# dlp_vco_v1_1_4_main.net
KiCad netlist of a schematic drawn in EAGLE
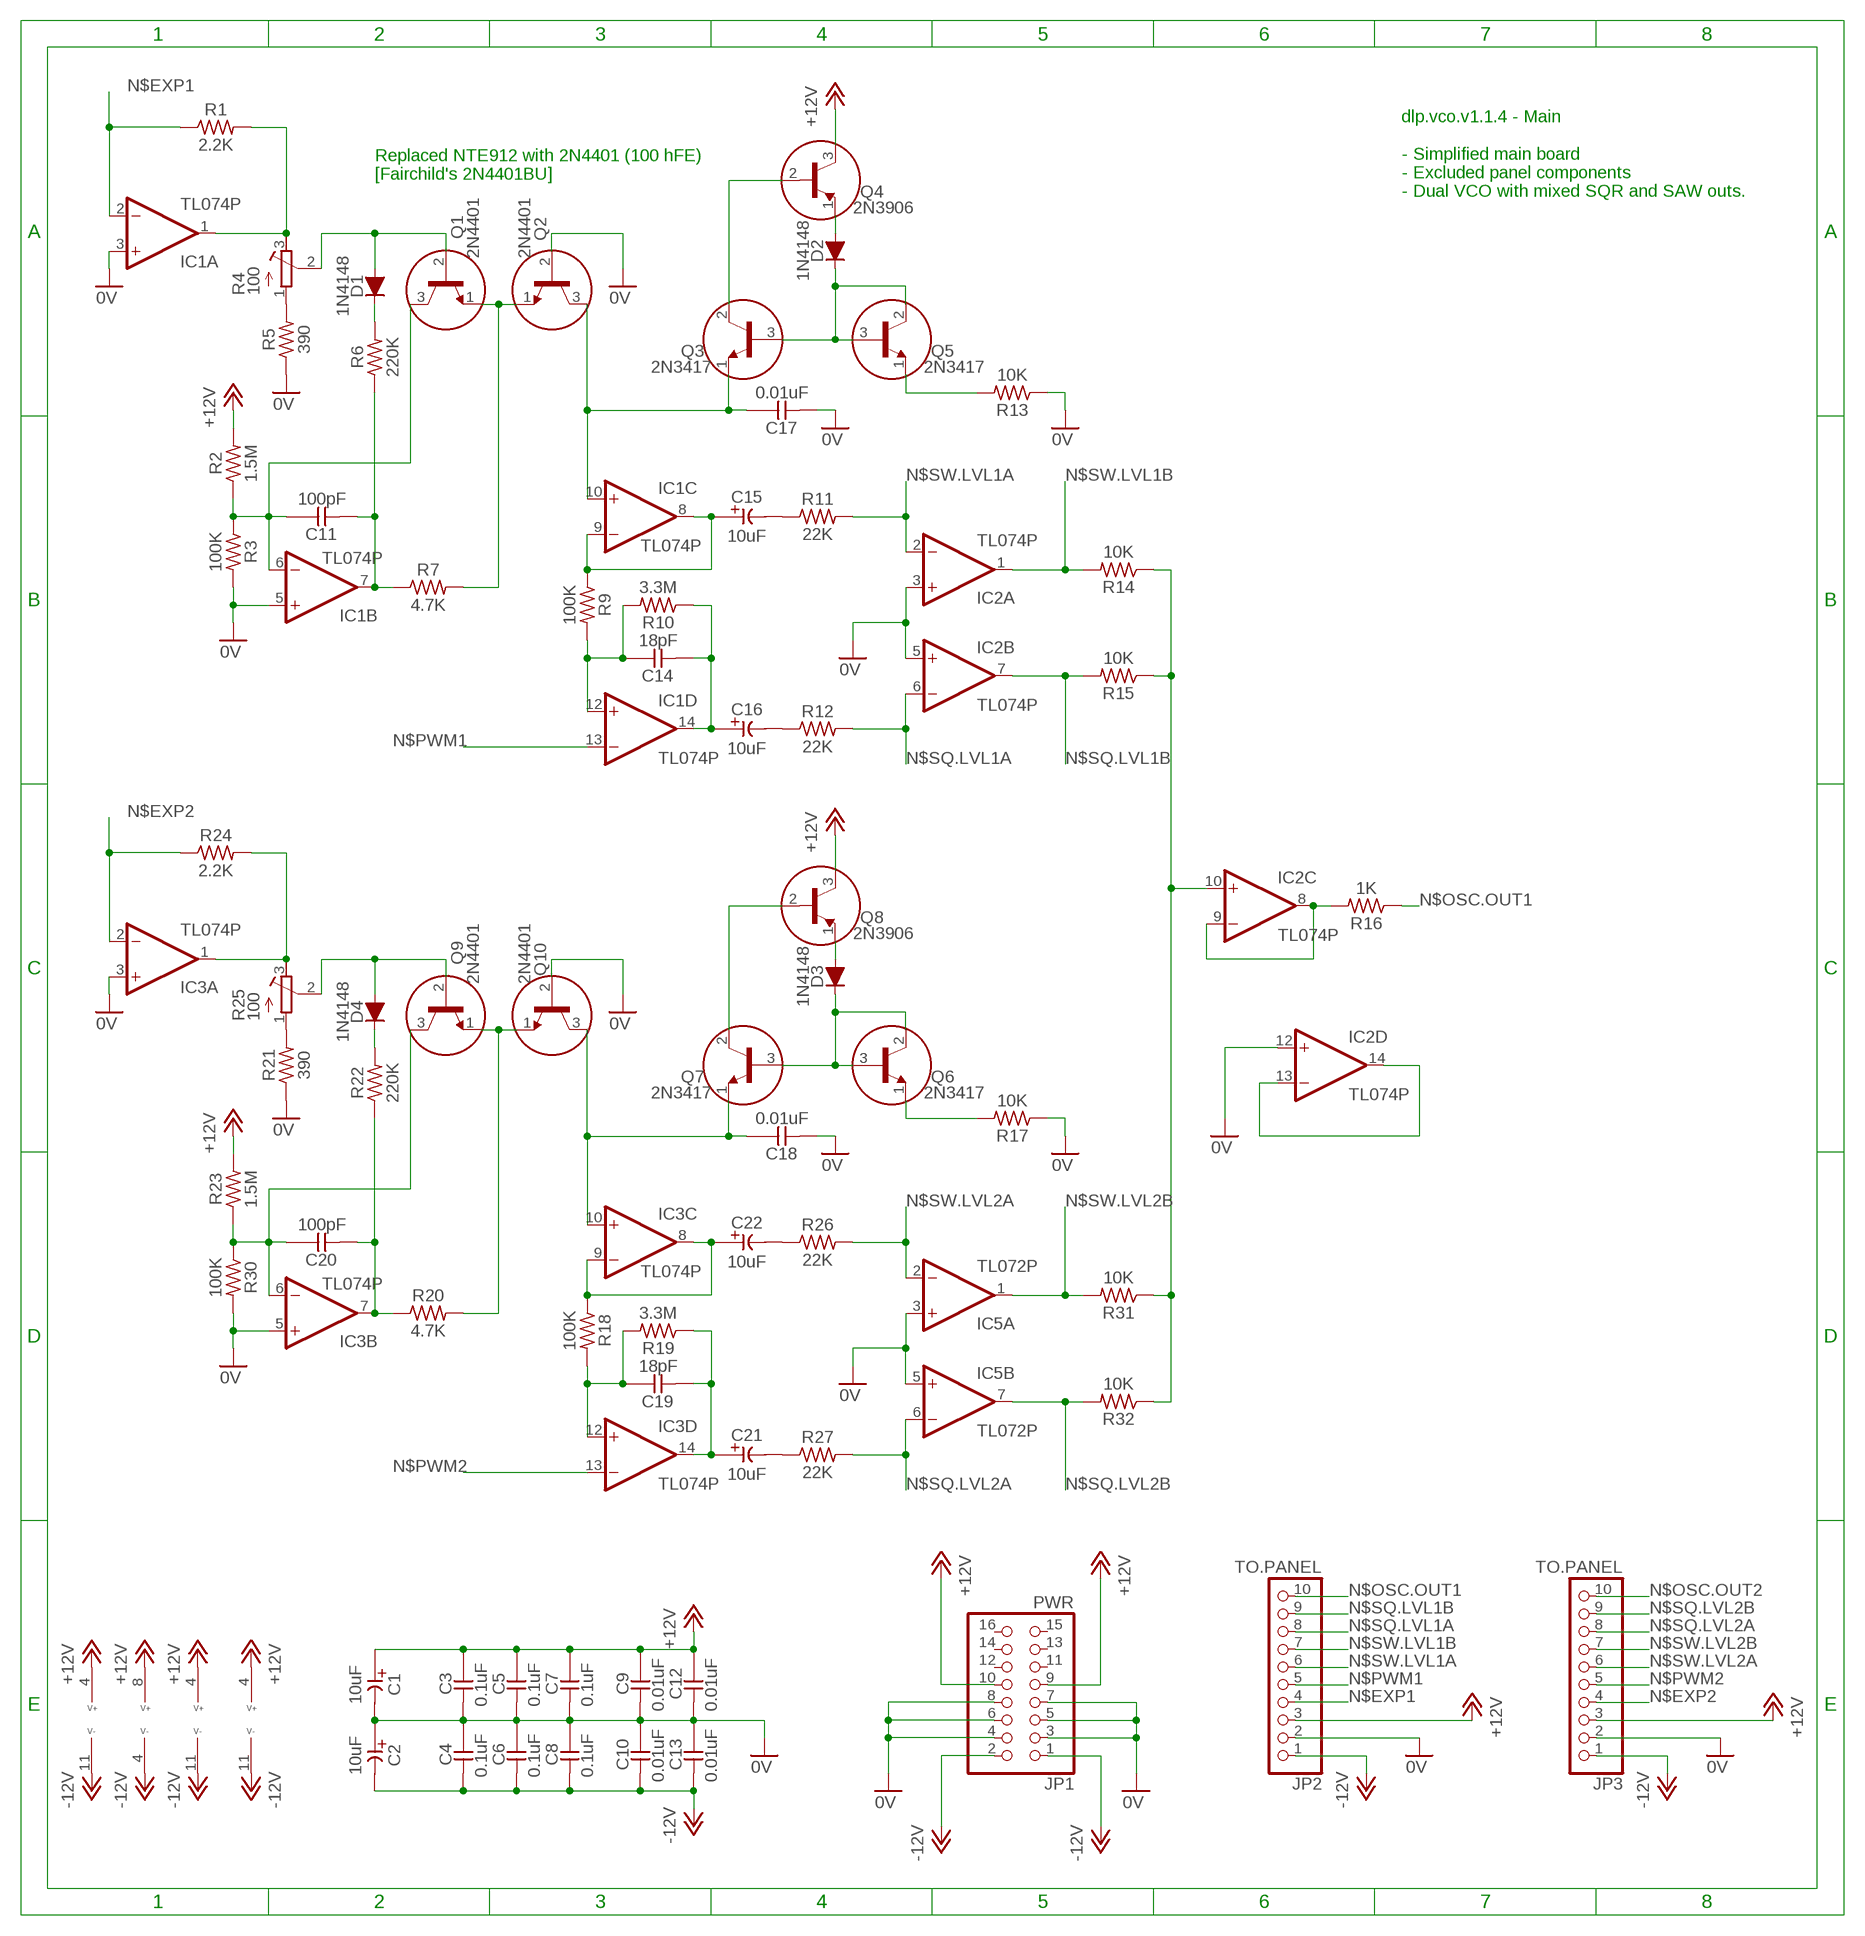
[diagram p0: schematic, sheet 1]

(export (version "E")
  (design (tool "Eeschema 10.0.6"))
  (components
    (comp (ref "C1")
      (value "10uF")
      (footprint "eagle-import:E2-5")
      (libsource (lib "eagle-import") (part "CE-USE2-5"))
    )
    (comp (ref "C2")
      (value "10uF")
      (footprint "eagle-import:E2-5")
      (libsource (lib "eagle-import") (part "CE-USE2-5"))
    )
    (comp (ref "C3")
      (value "0.1uF")
      (footprint "eagle-import:C025-024X044")
      (libsource (lib "eagle-import") (part "CC-US025-024X044"))
    )
    (comp (ref "C4")
      (value "0.1uF")
      (footprint "eagle-import:C025-024X044")
      (libsource (lib "eagle-import") (part "CC-US025-024X044"))
    )
    (comp (ref "C5")
      (value "0.1uF")
      (footprint "eagle-import:C025-024X044")
      (libsource (lib "eagle-import") (part "CC-US025-024X044"))
    )
    (comp (ref "C6")
      (value "0.1uF")
      (footprint "eagle-import:C025-024X044")
      (libsource (lib "eagle-import") (part "CC-US025-024X044"))
    )
    (comp (ref "C7")
      (value "0.1uF")
      (footprint "eagle-import:C025-024X044")
      (libsource (lib "eagle-import") (part "CC-US025-024X044"))
    )
    (comp (ref "C8")
      (value "0.1uF")
      (footprint "eagle-import:C025-024X044")
      (libsource (lib "eagle-import") (part "CC-US025-024X044"))
    )
    (comp (ref "C9")
      (value "0.01uF")
      (footprint "eagle-import:C025-024X044")
      (libsource (lib "eagle-import") (part "CC-US025-024X044"))
    )
    (comp (ref "C10")
      (value "0.01uF")
      (footprint "eagle-import:C025-024X044")
      (libsource (lib "eagle-import") (part "CC-US025-024X044"))
    )
    (comp (ref "C11")
      (value "100pF")
      (footprint "eagle-import:C025-024X044")
      (libsource (lib "eagle-import") (part "CC-US025-024X044"))
    )
    (comp (ref "C12")
      (value "0.01uF")
      (footprint "eagle-import:C025-024X044")
      (libsource (lib "eagle-import") (part "CC-US025-024X044"))
    )
    (comp (ref "C13")
      (value "0.01uF")
      (footprint "eagle-import:C025-024X044")
      (libsource (lib "eagle-import") (part "CC-US025-024X044"))
    )
    (comp (ref "C14")
      (value "18pF")
      (footprint "eagle-import:C025-024X044")
      (libsource (lib "eagle-import") (part "CC-US025-024X044"))
    )
    (comp (ref "C15")
      (value "10uF")
      (footprint "eagle-import:E2-5")
      (libsource (lib "eagle-import") (part "CE-USE2-5"))
    )
    (comp (ref "C16")
      (value "10uF")
      (footprint "eagle-import:E2-5")
      (libsource (lib "eagle-import") (part "CE-USE2-5"))
    )
    (comp (ref "C17")
      (value "0.01uF")
      (footprint "eagle-import:C025-024X044")
      (libsource (lib "eagle-import") (part "CC-US025-024X044"))
    )
    (comp (ref "C18")
      (value "0.01uF")
      (footprint "eagle-import:C025-024X044")
      (libsource (lib "eagle-import") (part "CC-US025-024X044"))
    )
    (comp (ref "C19")
      (value "18pF")
      (footprint "eagle-import:C025-024X044")
      (libsource (lib "eagle-import") (part "CC-US025-024X044"))
    )
    (comp (ref "C20")
      (value "100pF")
      (footprint "eagle-import:C025-024X044")
      (libsource (lib "eagle-import") (part "CC-US025-024X044"))
    )
    (comp (ref "C21")
      (value "10uF")
      (footprint "eagle-import:E2-5")
      (libsource (lib "eagle-import") (part "CE-USE2-5"))
    )
    (comp (ref "C22")
      (value "10uF")
      (footprint "eagle-import:E2-5")
      (libsource (lib "eagle-import") (part "CE-USE2-5"))
    )
    (comp (ref "D1")
      (value "1N4148")
      (footprint "eagle-import:DO35-7")
      (libsource (lib "eagle-import") (part "1N4148"))
    )
    (comp (ref "D2")
      (value "1N4148")
      (footprint "eagle-import:DO35-7")
      (libsource (lib "eagle-import") (part "1N4148"))
    )
    (comp (ref "D3")
      (value "1N4148")
      (footprint "eagle-import:DO35-7")
      (libsource (lib "eagle-import") (part "1N4148"))
    )
    (comp (ref "D4")
      (value "1N4148")
      (footprint "eagle-import:DO35-7")
      (libsource (lib "eagle-import") (part "1N4148"))
    )
    (comp (ref "IC1")
      (value "TL074P")
      (footprint "eagle-import:DIL14")
      (libsource (lib "eagle-import") (part "TL074P"))
    )
    (comp (ref "IC2")
      (value "TL074P")
      (footprint "eagle-import:DIL14")
      (libsource (lib "eagle-import") (part "TL074P"))
    )
    (comp (ref "IC3")
      (value "TL074P")
      (footprint "eagle-import:DIL14")
      (libsource (lib "eagle-import") (part "TL074P"))
    )
    (comp (ref "IC5")
      (value "TL072P")
      (footprint "eagle-import:DIL08")
      (libsource (lib "eagle-import") (part "TL072P"))
    )
    (comp (ref "JP1")
      (value "PWR")
      (footprint "eagle-import:2X08")
      (libsource (lib "eagle-import") (part "PINHD-2X8"))
    )
    (comp (ref "JP2")
      (value "TO.PANEL")
      (footprint "eagle-import:1X10")
      (libsource (lib "eagle-import") (part "PINHD-1X10"))
    )
    (comp (ref "JP3")
      (value "TO.PANEL")
      (footprint "eagle-import:1X10")
      (libsource (lib "eagle-import") (part "PINHD-1X10"))
    )
    (comp (ref "Q1")
      (value "2N4401")
      (footprint "eagle-import:TO92")
      (libsource (lib "eagle-import") (part "2N4401"))
    )
    (comp (ref "Q2")
      (value "2N4401")
      (footprint "eagle-import:TO92")
      (libsource (lib "eagle-import") (part "2N4401"))
    )
    (comp (ref "Q3")
      (value "2N3417")
      (footprint "eagle-import:TO92")
      (libsource (lib "eagle-import") (part "2N3417"))
    )
    (comp (ref "Q4")
      (value "2N3906")
      (footprint "eagle-import:TO92")
      (libsource (lib "eagle-import") (part "2N3906"))
    )
    (comp (ref "Q5")
      (value "2N3417")
      (footprint "eagle-import:TO92")
      (libsource (lib "eagle-import") (part "2N3417"))
    )
    (comp (ref "Q6")
      (value "2N3417")
      (footprint "eagle-import:TO92")
      (libsource (lib "eagle-import") (part "2N3417"))
    )
    (comp (ref "Q7")
      (value "2N3417")
      (footprint "eagle-import:TO92")
      (libsource (lib "eagle-import") (part "2N3417"))
    )
    (comp (ref "Q8")
      (value "2N3906")
      (footprint "eagle-import:TO92")
      (libsource (lib "eagle-import") (part "2N3906"))
    )
    (comp (ref "Q9")
      (value "2N4401")
      (footprint "eagle-import:TO92")
      (libsource (lib "eagle-import") (part "2N4401"))
    )
    (comp (ref "Q10")
      (value "2N4401")
      (footprint "eagle-import:TO92")
      (libsource (lib "eagle-import") (part "2N4401"))
    )
    (comp (ref "R1")
      (value "2.2K")
      (footprint "eagle-import:0309_10")
      (libsource (lib "eagle-import") (part "R0309/10"))
    )
    (comp (ref "R2")
      (value "1.5M")
      (footprint "eagle-import:0309_10")
      (libsource (lib "eagle-import") (part "R0309/10"))
    )
    (comp (ref "R3")
      (value "100K")
      (footprint "eagle-import:0309_10")
      (libsource (lib "eagle-import") (part "R0309/10"))
    )
    (comp (ref "R4")
      (value "100")
      (footprint "eagle-import:RTRIM3296Y")
      (libsource (lib "eagle-import") (part "R-TRIMM3296Y"))
    )
    (comp (ref "R5")
      (value "390")
      (footprint "eagle-import:0309_10")
      (libsource (lib "eagle-import") (part "R0309/10"))
    )
    (comp (ref "R6")
      (value "220K")
      (footprint "eagle-import:0309_10")
      (libsource (lib "eagle-import") (part "R0309/10"))
    )
    (comp (ref "R7")
      (value "4.7K")
      (footprint "eagle-import:0309_10")
      (libsource (lib "eagle-import") (part "R0309/10"))
    )
    (comp (ref "R9")
      (value "100K")
      (footprint "eagle-import:0309_10")
      (libsource (lib "eagle-import") (part "R0309/10"))
    )
    (comp (ref "R10")
      (value "3.3M")
      (footprint "eagle-import:0309_10")
      (libsource (lib "eagle-import") (part "R0309/10"))
    )
    (comp (ref "R11")
      (value "22K")
      (footprint "eagle-import:0309_10")
      (libsource (lib "eagle-import") (part "R0309/10"))
    )
    (comp (ref "R12")
      (value "22K")
      (footprint "eagle-import:0309_10")
      (libsource (lib "eagle-import") (part "R0309/10"))
    )
    (comp (ref "R13")
      (value "10K")
      (footprint "eagle-import:0309_10")
      (libsource (lib "eagle-import") (part "R0309/10"))
    )
    (comp (ref "R14")
      (value "10K")
      (footprint "eagle-import:0309_10")
      (libsource (lib "eagle-import") (part "R0309/10"))
    )
    (comp (ref "R15")
      (value "10K")
      (footprint "eagle-import:0309_10")
      (libsource (lib "eagle-import") (part "R0309/10"))
    )
    (comp (ref "R16")
      (value "1K")
      (footprint "eagle-import:0309_10")
      (libsource (lib "eagle-import") (part "R0309/10"))
    )
    (comp (ref "R17")
      (value "10K")
      (footprint "eagle-import:0309_10")
      (libsource (lib "eagle-import") (part "R0309/10"))
    )
    (comp (ref "R18")
      (value "100K")
      (footprint "eagle-import:0309_10")
      (libsource (lib "eagle-import") (part "R0309/10"))
    )
    (comp (ref "R19")
      (value "3.3M")
      (footprint "eagle-import:0309_10")
      (libsource (lib "eagle-import") (part "R0309/10"))
    )
    (comp (ref "R20")
      (value "4.7K")
      (footprint "eagle-import:0309_10")
      (libsource (lib "eagle-import") (part "R0309/10"))
    )
    (comp (ref "R21")
      (value "390")
      (footprint "eagle-import:0309_10")
      (libsource (lib "eagle-import") (part "R0309/10"))
    )
    (comp (ref "R22")
      (value "220K")
      (footprint "eagle-import:0309_10")
      (libsource (lib "eagle-import") (part "R0309/10"))
    )
    (comp (ref "R23")
      (value "1.5M")
      (footprint "eagle-import:0309_10")
      (libsource (lib "eagle-import") (part "R0309/10"))
    )
    (comp (ref "R24")
      (value "2.2K")
      (footprint "eagle-import:0309_10")
      (libsource (lib "eagle-import") (part "R0309/10"))
    )
    (comp (ref "R25")
      (value "100")
      (footprint "eagle-import:RTRIM3296Y")
      (libsource (lib "eagle-import") (part "R-TRIMM3296Y"))
    )
    (comp (ref "R26")
      (value "22K")
      (footprint "eagle-import:0309_10")
      (libsource (lib "eagle-import") (part "R0309/10"))
    )
    (comp (ref "R27")
      (value "22K")
      (footprint "eagle-import:0309_10")
      (libsource (lib "eagle-import") (part "R0309/10"))
    )
    (comp (ref "R30")
      (value "100K")
      (footprint "eagle-import:0309_10")
      (libsource (lib "eagle-import") (part "R0309/10"))
    )
    (comp (ref "R31")
      (value "10K")
      (footprint "eagle-import:0309_10")
      (libsource (lib "eagle-import") (part "R0309/10"))
    )
    (comp (ref "R32")
      (value "10K")
      (footprint "eagle-import:0309_10")
      (libsource (lib "eagle-import") (part "R0309/10"))
    )
  )
  (nets
    (net (code "1") (name "+12V") (class "Default")
      (node (ref "C1") (pin "+") (pinfunction "+_+") (pintype "passive"))
      (node (ref "C12") (pin "1") (pinfunction "1_1") (pintype "passive"))
      (node (ref "C3") (pin "1") (pinfunction "1_1") (pintype "passive"))
      (node (ref "C5") (pin "1") (pinfunction "1_1") (pintype "passive"))
      (node (ref "C7") (pin "1") (pinfunction "1_1") (pintype "passive"))
      (node (ref "C9") (pin "1") (pinfunction "1_1") (pintype "passive"))
      (node (ref "IC1") (pin "4") (pinfunction "V+_4") (pintype "power_in"))
      (node (ref "IC2") (pin "4") (pinfunction "V+_4") (pintype "power_in"))
      (node (ref "IC3") (pin "4") (pinfunction "V+_4") (pintype "power_in"))
      (node (ref "IC5") (pin "8") (pinfunction "V+_8") (pintype "power_in"))
      (node (ref "JP1") (pin "10") (pinfunction "10_10") (pintype "passive"))
      (node (ref "JP1") (pin "9") (pinfunction "9_9") (pintype "passive"))
      (node (ref "JP2") (pin "3") (pinfunction "3_3") (pintype "passive"))
      (node (ref "JP3") (pin "3") (pinfunction "3_3") (pintype "passive"))
      (node (ref "Q4") (pin "3") (pinfunction "C_3") (pintype "passive"))
      (node (ref "Q8") (pin "3") (pinfunction "C_3") (pintype "passive"))
      (node (ref "R2") (pin "2") (pinfunction "2_2") (pintype "passive"))
      (node (ref "R23") (pin "2") (pinfunction "2_2") (pintype "passive"))
    )
    (net (code "2") (name "-12V") (class "Default")
      (node (ref "C10") (pin "2") (pinfunction "2_2") (pintype "passive"))
      (node (ref "C13") (pin "2") (pinfunction "2_2") (pintype "passive"))
      (node (ref "C2") (pin "-") (pinfunction "-_-") (pintype "passive"))
      (node (ref "C4") (pin "2") (pinfunction "2_2") (pintype "passive"))
      (node (ref "C6") (pin "2") (pinfunction "2_2") (pintype "passive"))
      (node (ref "C8") (pin "2") (pinfunction "2_2") (pintype "passive"))
      (node (ref "IC1") (pin "11") (pinfunction "V-_11") (pintype "power_in"))
      (node (ref "IC2") (pin "11") (pinfunction "V-_11") (pintype "power_in"))
      (node (ref "IC3") (pin "11") (pinfunction "V-_11") (pintype "power_in"))
      (node (ref "IC5") (pin "4") (pinfunction "V-_4") (pintype "power_in"))
      (node (ref "JP1") (pin "1") (pinfunction "1_1") (pintype "passive"))
      (node (ref "JP1") (pin "2") (pinfunction "2_2") (pintype "passive"))
      (node (ref "JP2") (pin "1") (pinfunction "1_1") (pintype "passive"))
      (node (ref "JP3") (pin "1") (pinfunction "1_1") (pintype "passive"))
    )
    (net (code "3") (name "/N$EXP1") (class "Default")
      (node (ref "IC1") (pin "2") (pinfunction "-IN_2") (pintype "input"))
      (node (ref "JP2") (pin "4") (pinfunction "4_4") (pintype "passive"))
      (node (ref "R1") (pin "1") (pinfunction "1_1") (pintype "passive"))
    )
    (net (code "4") (name "/N$EXP2") (class "Default")
      (node (ref "IC3") (pin "2") (pinfunction "-IN_2") (pintype "input"))
      (node (ref "JP3") (pin "4") (pinfunction "4_4") (pintype "passive"))
      (node (ref "R24") (pin "1") (pinfunction "1_1") (pintype "passive"))
    )
    (net (code "5") (name "/N$OSC.OUT1") (class "Default")
      (node (ref "JP2") (pin "10") (pinfunction "10_10") (pintype "passive"))
      (node (ref "R16") (pin "1") (pinfunction "1_1") (pintype "passive"))
    )
    (net (code "6") (name "/N$OSC.OUT2") (class "Default")
      (node (ref "JP3") (pin "10") (pinfunction "10_10") (pintype "passive"))
    )
    (net (code "7") (name "/N$PWM1") (class "Default")
      (node (ref "IC1") (pin "13") (pinfunction "-IN_13") (pintype "input"))
      (node (ref "JP2") (pin "5") (pinfunction "5_5") (pintype "passive"))
    )
    (net (code "8") (name "/N$PWM2") (class "Default")
      (node (ref "IC3") (pin "13") (pinfunction "-IN_13") (pintype "input"))
      (node (ref "JP3") (pin "5") (pinfunction "5_5") (pintype "passive"))
    )
    (net (code "9") (name "/N$SQ.LVL1A") (class "Default")
      (node (ref "IC2") (pin "6") (pinfunction "-IN_6") (pintype "input"))
      (node (ref "JP2") (pin "8") (pinfunction "8_8") (pintype "passive"))
      (node (ref "R12") (pin "2") (pinfunction "2_2") (pintype "passive"))
    )
    (net (code "10") (name "/N$SQ.LVL1B") (class "Default")
      (node (ref "IC2") (pin "7") (pinfunction "OUT_7") (pintype "output"))
      (node (ref "JP2") (pin "9") (pinfunction "9_9") (pintype "passive"))
      (node (ref "R15") (pin "2") (pinfunction "2_2") (pintype "passive"))
    )
    (net (code "11") (name "/N$SQ.LVL2A") (class "Default")
      (node (ref "IC5") (pin "6") (pinfunction "-IN_6") (pintype "input"))
      (node (ref "JP3") (pin "8") (pinfunction "8_8") (pintype "passive"))
      (node (ref "R27") (pin "2") (pinfunction "2_2") (pintype "passive"))
    )
    (net (code "12") (name "/N$SQ.LVL2B") (class "Default")
      (node (ref "IC5") (pin "7") (pinfunction "OUT_7") (pintype "output"))
      (node (ref "JP3") (pin "9") (pinfunction "9_9") (pintype "passive"))
      (node (ref "R32") (pin "2") (pinfunction "2_2") (pintype "passive"))
    )
    (net (code "13") (name "/N$SW.LVL1A") (class "Default")
      (node (ref "IC2") (pin "2") (pinfunction "-IN_2") (pintype "input"))
      (node (ref "JP2") (pin "6") (pinfunction "6_6") (pintype "passive"))
      (node (ref "R11") (pin "2") (pinfunction "2_2") (pintype "passive"))
    )
    (net (code "14") (name "/N$SW.LVL1B") (class "Default")
      (node (ref "IC2") (pin "1") (pinfunction "OUT_1") (pintype "output"))
      (node (ref "JP2") (pin "7") (pinfunction "7_7") (pintype "passive"))
      (node (ref "R14") (pin "2") (pinfunction "2_2") (pintype "passive"))
    )
    (net (code "15") (name "/N$SW.LVL2A") (class "Default")
      (node (ref "IC5") (pin "2") (pinfunction "-IN_2") (pintype "input"))
      (node (ref "JP3") (pin "6") (pinfunction "6_6") (pintype "passive"))
      (node (ref "R26") (pin "2") (pinfunction "2_2") (pintype "passive"))
    )
    (net (code "16") (name "/N$SW.LVL2B") (class "Default")
      (node (ref "IC5") (pin "1") (pinfunction "OUT_1") (pintype "output"))
      (node (ref "JP3") (pin "7") (pinfunction "7_7") (pintype "passive"))
      (node (ref "R31") (pin "2") (pinfunction "2_2") (pintype "passive"))
    )
    (net (code "17") (name "0V") (class "Default")
      (node (ref "C1") (pin "-") (pinfunction "-_-") (pintype "passive"))
      (node (ref "C10") (pin "1") (pinfunction "1_1") (pintype "passive"))
      (node (ref "C12") (pin "2") (pinfunction "2_2") (pintype "passive"))
      (node (ref "C13") (pin "1") (pinfunction "1_1") (pintype "passive"))
      (node (ref "C17") (pin "2") (pinfunction "2_2") (pintype "passive"))
      (node (ref "C18") (pin "2") (pinfunction "2_2") (pintype "passive"))
      (node (ref "C2") (pin "+") (pinfunction "+_+") (pintype "passive"))
      (node (ref "C3") (pin "2") (pinfunction "2_2") (pintype "passive"))
      (node (ref "C4") (pin "1") (pinfunction "1_1") (pintype "passive"))
      (node (ref "C5") (pin "2") (pinfunction "2_2") (pintype "passive"))
      (node (ref "C6") (pin "1") (pinfunction "1_1") (pintype "passive"))
      (node (ref "C7") (pin "2") (pinfunction "2_2") (pintype "passive"))
      (node (ref "C8") (pin "1") (pinfunction "1_1") (pintype "passive"))
      (node (ref "C9") (pin "2") (pinfunction "2_2") (pintype "passive"))
      (node (ref "IC1") (pin "3") (pinfunction "+IN_3") (pintype "input"))
      (node (ref "IC1") (pin "5") (pinfunction "+IN_5") (pintype "input"))
      (node (ref "IC2") (pin "12") (pinfunction "+IN_12") (pintype "input"))
      (node (ref "IC2") (pin "3") (pinfunction "+IN_3") (pintype "input"))
      (node (ref "IC2") (pin "5") (pinfunction "+IN_5") (pintype "input"))
      (node (ref "IC3") (pin "3") (pinfunction "+IN_3") (pintype "input"))
      (node (ref "IC3") (pin "5") (pinfunction "+IN_5") (pintype "input"))
      (node (ref "IC5") (pin "3") (pinfunction "+IN_3") (pintype "input"))
      (node (ref "IC5") (pin "5") (pinfunction "+IN_5") (pintype "input"))
      (node (ref "JP1") (pin "3") (pinfunction "3_3") (pintype "passive"))
      (node (ref "JP1") (pin "4") (pinfunction "4_4") (pintype "passive"))
      (node (ref "JP1") (pin "5") (pinfunction "5_5") (pintype "passive"))
      (node (ref "JP1") (pin "6") (pinfunction "6_6") (pintype "passive"))
      (node (ref "JP1") (pin "7") (pinfunction "7_7") (pintype "passive"))
      (node (ref "JP1") (pin "8") (pinfunction "8_8") (pintype "passive"))
      (node (ref "JP2") (pin "2") (pinfunction "2_2") (pintype "passive"))
      (node (ref "JP3") (pin "2") (pinfunction "2_2") (pintype "passive"))
      (node (ref "Q10") (pin "2") (pinfunction "B_2") (pintype "passive"))
      (node (ref "Q2") (pin "2") (pinfunction "B_2") (pintype "passive"))
      (node (ref "R13") (pin "1") (pinfunction "1_1") (pintype "passive"))
      (node (ref "R17") (pin "1") (pinfunction "1_1") (pintype "passive"))
      (node (ref "R21") (pin "1") (pinfunction "1_1") (pintype "passive"))
      (node (ref "R3") (pin "2") (pinfunction "2_2") (pintype "passive"))
      (node (ref "R30") (pin "2") (pinfunction "2_2") (pintype "passive"))
      (node (ref "R5") (pin "1") (pinfunction "1_1") (pintype "passive"))
    )
    (net (code "18") (name "Net-(C15-Pad-)") (class "Default")
      (node (ref "C15") (pin "-") (pinfunction "-_-") (pintype "passive"))
      (node (ref "R11") (pin "1") (pinfunction "1_1") (pintype "passive"))
    )
    (net (code "19") (name "Net-(C16-Pad-)") (class "Default")
      (node (ref "C16") (pin "-") (pinfunction "-_-") (pintype "passive"))
      (node (ref "R12") (pin "1") (pinfunction "1_1") (pintype "passive"))
    )
    (net (code "20") (name "Net-(C21-Pad-)") (class "Default")
      (node (ref "C21") (pin "-") (pinfunction "-_-") (pintype "passive"))
      (node (ref "R27") (pin "1") (pinfunction "1_1") (pintype "passive"))
    )
    (net (code "21") (name "Net-(C22-Pad-)") (class "Default")
      (node (ref "C22") (pin "-") (pinfunction "-_-") (pintype "passive"))
      (node (ref "R26") (pin "1") (pinfunction "1_1") (pintype "passive"))
    )
    (net (code "22") (name "Net-(D1-PadC)") (class "Default")
      (node (ref "D1") (pin "C") (pinfunction "C_C") (pintype "passive"))
      (node (ref "R6") (pin "2") (pinfunction "2_2") (pintype "passive"))
    )
    (net (code "23") (name "Net-(D4-PadC)") (class "Default")
      (node (ref "D4") (pin "C") (pinfunction "C_C") (pintype "passive"))
      (node (ref "R22") (pin "2") (pinfunction "2_2") (pintype "passive"))
    )
    (net (code "24") (name "Net-(IC1A-OUT)") (class "Default")
      (node (ref "IC1") (pin "1") (pinfunction "OUT_1") (pintype "output"))
      (node (ref "R1") (pin "2") (pinfunction "2_2") (pintype "passive"))
      (node (ref "R4") (pin "3") (pinfunction "E_3") (pintype "passive"))
    )
    (net (code "25") (name "Net-(IC1B--IN)") (class "Default")
      (node (ref "C11") (pin "1") (pinfunction "1_1") (pintype "passive"))
      (node (ref "IC1") (pin "6") (pinfunction "-IN_6") (pintype "input"))
      (node (ref "Q1") (pin "3") (pinfunction "C_3") (pintype "passive"))
      (node (ref "R2") (pin "1") (pinfunction "1_1") (pintype "passive"))
      (node (ref "R3") (pin "1") (pinfunction "1_1") (pintype "passive"))
    )
    (net (code "26") (name "Net-(IC1B-OUT)") (class "Default")
      (node (ref "C11") (pin "2") (pinfunction "2_2") (pintype "passive"))
      (node (ref "IC1") (pin "7") (pinfunction "OUT_7") (pintype "output"))
      (node (ref "R6") (pin "1") (pinfunction "1_1") (pintype "passive"))
      (node (ref "R7") (pin "1") (pinfunction "1_1") (pintype "passive"))
    )
    (net (code "27") (name "Net-(IC1C-+IN)") (class "Default")
      (node (ref "C17") (pin "1") (pinfunction "1_1") (pintype "passive"))
      (node (ref "IC1") (pin "10") (pinfunction "+IN_10") (pintype "input"))
      (node (ref "Q2") (pin "3") (pinfunction "C_3") (pintype "passive"))
      (node (ref "Q3") (pin "1") (pinfunction "E_1") (pintype "passive"))
    )
    (net (code "28") (name "Net-(IC1C--IN)") (class "Default")
      (node (ref "C15") (pin "+") (pinfunction "+_+") (pintype "passive"))
      (node (ref "IC1") (pin "8") (pinfunction "OUT_8") (pintype "output"))
      (node (ref "IC1") (pin "9") (pinfunction "-IN_9") (pintype "input"))
      (node (ref "R9") (pin "1") (pinfunction "1_1") (pintype "passive"))
    )
    (net (code "29") (name "Net-(IC1D-+IN)") (class "Default")
      (node (ref "C14") (pin "1") (pinfunction "1_1") (pintype "passive"))
      (node (ref "IC1") (pin "12") (pinfunction "+IN_12") (pintype "input"))
      (node (ref "R10") (pin "2") (pinfunction "2_2") (pintype "passive"))
      (node (ref "R9") (pin "2") (pinfunction "2_2") (pintype "passive"))
    )
    (net (code "30") (name "Net-(IC1D-OUT)") (class "Default")
      (node (ref "C14") (pin "2") (pinfunction "2_2") (pintype "passive"))
      (node (ref "C16") (pin "+") (pinfunction "+_+") (pintype "passive"))
      (node (ref "IC1") (pin "14") (pinfunction "OUT_14") (pintype "output"))
      (node (ref "R10") (pin "1") (pinfunction "1_1") (pintype "passive"))
    )
    (net (code "31") (name "Net-(IC2C-+IN)") (class "Default")
      (node (ref "IC2") (pin "10") (pinfunction "+IN_10") (pintype "input"))
      (node (ref "R14") (pin "1") (pinfunction "1_1") (pintype "passive"))
      (node (ref "R15") (pin "1") (pinfunction "1_1") (pintype "passive"))
      (node (ref "R31") (pin "1") (pinfunction "1_1") (pintype "passive"))
      (node (ref "R32") (pin "1") (pinfunction "1_1") (pintype "passive"))
    )
    (net (code "32") (name "Net-(IC2C--IN)") (class "Default")
      (node (ref "IC2") (pin "8") (pinfunction "OUT_8") (pintype "output"))
      (node (ref "IC2") (pin "9") (pinfunction "-IN_9") (pintype "input"))
      (node (ref "R16") (pin "2") (pinfunction "2_2") (pintype "passive"))
    )
    (net (code "33") (name "Net-(IC2D--IN)") (class "Default")
      (node (ref "IC2") (pin "13") (pinfunction "-IN_13") (pintype "input"))
      (node (ref "IC2") (pin "14") (pinfunction "OUT_14") (pintype "output"))
    )
    (net (code "34") (name "Net-(IC3A-OUT)") (class "Default")
      (node (ref "IC3") (pin "1") (pinfunction "OUT_1") (pintype "output"))
      (node (ref "R24") (pin "2") (pinfunction "2_2") (pintype "passive"))
      (node (ref "R25") (pin "3") (pinfunction "E_3") (pintype "passive"))
    )
    (net (code "35") (name "Net-(IC3B--IN)") (class "Default")
      (node (ref "C20") (pin "1") (pinfunction "1_1") (pintype "passive"))
      (node (ref "IC3") (pin "6") (pinfunction "-IN_6") (pintype "input"))
      (node (ref "Q9") (pin "3") (pinfunction "C_3") (pintype "passive"))
      (node (ref "R23") (pin "1") (pinfunction "1_1") (pintype "passive"))
      (node (ref "R30") (pin "1") (pinfunction "1_1") (pintype "passive"))
    )
    (net (code "36") (name "Net-(IC3B-OUT)") (class "Default")
      (node (ref "C20") (pin "2") (pinfunction "2_2") (pintype "passive"))
      (node (ref "IC3") (pin "7") (pinfunction "OUT_7") (pintype "output"))
      (node (ref "R20") (pin "1") (pinfunction "1_1") (pintype "passive"))
      (node (ref "R22") (pin "1") (pinfunction "1_1") (pintype "passive"))
    )
    (net (code "37") (name "Net-(IC3C-+IN)") (class "Default")
      (node (ref "C18") (pin "1") (pinfunction "1_1") (pintype "passive"))
      (node (ref "IC3") (pin "10") (pinfunction "+IN_10") (pintype "input"))
      (node (ref "Q10") (pin "3") (pinfunction "C_3") (pintype "passive"))
      (node (ref "Q7") (pin "1") (pinfunction "E_1") (pintype "passive"))
    )
    (net (code "38") (name "Net-(IC3C--IN)") (class "Default")
      (node (ref "C22") (pin "+") (pinfunction "+_+") (pintype "passive"))
      (node (ref "IC3") (pin "8") (pinfunction "OUT_8") (pintype "output"))
      (node (ref "IC3") (pin "9") (pinfunction "-IN_9") (pintype "input"))
      (node (ref "R18") (pin "1") (pinfunction "1_1") (pintype "passive"))
    )
    (net (code "39") (name "Net-(IC3D-+IN)") (class "Default")
      (node (ref "C19") (pin "1") (pinfunction "1_1") (pintype "passive"))
      (node (ref "IC3") (pin "12") (pinfunction "+IN_12") (pintype "input"))
      (node (ref "R18") (pin "2") (pinfunction "2_2") (pintype "passive"))
      (node (ref "R19") (pin "2") (pinfunction "2_2") (pintype "passive"))
    )
    (net (code "40") (name "Net-(IC3D-OUT)") (class "Default")
      (node (ref "C19") (pin "2") (pinfunction "2_2") (pintype "passive"))
      (node (ref "C21") (pin "+") (pinfunction "+_+") (pintype "passive"))
      (node (ref "IC3") (pin "14") (pinfunction "OUT_14") (pintype "output"))
      (node (ref "R19") (pin "1") (pinfunction "1_1") (pintype "passive"))
    )
    (net (code "41") (name "Net-(Q1-B)") (class "Default")
      (node (ref "D1") (pin "A") (pinfunction "A_A") (pintype "passive"))
      (node (ref "Q1") (pin "2") (pinfunction "B_2") (pintype "passive"))
      (node (ref "R4") (pin "2") (pinfunction "S_2") (pintype "passive"))
    )
    (net (code "42") (name "Net-(Q1-E)") (class "Default")
      (node (ref "Q1") (pin "1") (pinfunction "E_1") (pintype "passive"))
      (node (ref "Q2") (pin "1") (pinfunction "E_1") (pintype "passive"))
      (node (ref "R7") (pin "2") (pinfunction "2_2") (pintype "passive"))
    )
    (net (code "43") (name "Net-(Q3-B)") (class "Default")
      (node (ref "D2") (pin "C") (pinfunction "C_C") (pintype "passive"))
      (node (ref "Q3") (pin "3") (pinfunction "B_3") (pintype "passive"))
      (node (ref "Q5") (pin "2") (pinfunction "C_2") (pintype "passive"))
      (node (ref "Q5") (pin "3") (pinfunction "B_3") (pintype "passive"))
    )
    (net (code "44") (name "Net-(Q3-C)") (class "Default")
      (node (ref "Q3") (pin "2") (pinfunction "C_2") (pintype "passive"))
      (node (ref "Q4") (pin "2") (pinfunction "B_2") (pintype "passive"))
    )
    (net (code "45") (name "Net-(Q4-E)") (class "Default")
      (node (ref "D2") (pin "A") (pinfunction "A_A") (pintype "passive"))
      (node (ref "Q4") (pin "1") (pinfunction "E_1") (pintype "passive"))
    )
    (net (code "46") (name "Net-(Q5-E)") (class "Default")
      (node (ref "Q5") (pin "1") (pinfunction "E_1") (pintype "passive"))
      (node (ref "R13") (pin "2") (pinfunction "2_2") (pintype "passive"))
    )
    (net (code "47") (name "Net-(Q6-B)") (class "Default")
      (node (ref "D3") (pin "C") (pinfunction "C_C") (pintype "passive"))
      (node (ref "Q6") (pin "2") (pinfunction "C_2") (pintype "passive"))
      (node (ref "Q6") (pin "3") (pinfunction "B_3") (pintype "passive"))
      (node (ref "Q7") (pin "3") (pinfunction "B_3") (pintype "passive"))
    )
    (net (code "48") (name "Net-(Q6-E)") (class "Default")
      (node (ref "Q6") (pin "1") (pinfunction "E_1") (pintype "passive"))
      (node (ref "R17") (pin "2") (pinfunction "2_2") (pintype "passive"))
    )
    (net (code "49") (name "Net-(Q7-C)") (class "Default")
      (node (ref "Q7") (pin "2") (pinfunction "C_2") (pintype "passive"))
      (node (ref "Q8") (pin "2") (pinfunction "B_2") (pintype "passive"))
    )
    (net (code "50") (name "Net-(Q8-E)") (class "Default")
      (node (ref "D3") (pin "A") (pinfunction "A_A") (pintype "passive"))
      (node (ref "Q8") (pin "1") (pinfunction "E_1") (pintype "passive"))
    )
    (net (code "51") (name "Net-(Q9-B)") (class "Default")
      (node (ref "D4") (pin "A") (pinfunction "A_A") (pintype "passive"))
      (node (ref "Q9") (pin "2") (pinfunction "B_2") (pintype "passive"))
      (node (ref "R25") (pin "2") (pinfunction "S_2") (pintype "passive"))
    )
    (net (code "52") (name "Net-(Q10-E)") (class "Default")
      (node (ref "Q10") (pin "1") (pinfunction "E_1") (pintype "passive"))
      (node (ref "Q9") (pin "1") (pinfunction "E_1") (pintype "passive"))
      (node (ref "R20") (pin "2") (pinfunction "2_2") (pintype "passive"))
    )
    (net (code "53") (name "Net-(R4-A)") (class "Default")
      (node (ref "R4") (pin "1") (pinfunction "A_1") (pintype "passive"))
      (node (ref "R5") (pin "2") (pinfunction "2_2") (pintype "passive"))
    )
    (net (code "54") (name "Net-(R25-A)") (class "Default")
      (node (ref "R21") (pin "2") (pinfunction "2_2") (pintype "passive"))
      (node (ref "R25") (pin "1") (pinfunction "A_1") (pintype "passive"))
    )
    (net (code "55") (name "unconnected-(JP1-Pad11)") (class "Default")
      (node (ref "JP1") (pin "11") (pinfunction "11_11") (pintype "passive"))
    )
    (net (code "56") (name "unconnected-(JP1-Pad12)") (class "Default")
      (node (ref "JP1") (pin "12") (pinfunction "12_12") (pintype "passive"))
    )
    (net (code "57") (name "unconnected-(JP1-Pad13)") (class "Default")
      (node (ref "JP1") (pin "13") (pinfunction "13_13") (pintype "passive"))
    )
    (net (code "58") (name "unconnected-(JP1-Pad14)") (class "Default")
      (node (ref "JP1") (pin "14") (pinfunction "14_14") (pintype "passive"))
    )
    (net (code "59") (name "unconnected-(JP1-Pad15)") (class "Default")
      (node (ref "JP1") (pin "15") (pinfunction "15_15") (pintype "passive"))
    )
    (net (code "60") (name "unconnected-(JP1-Pad16)") (class "Default")
      (node (ref "JP1") (pin "16") (pinfunction "16_16") (pintype "passive"))
    )
  )
)
